# Power_supplies.net
KiCad netlist of a schematic drawn in Altium Designer
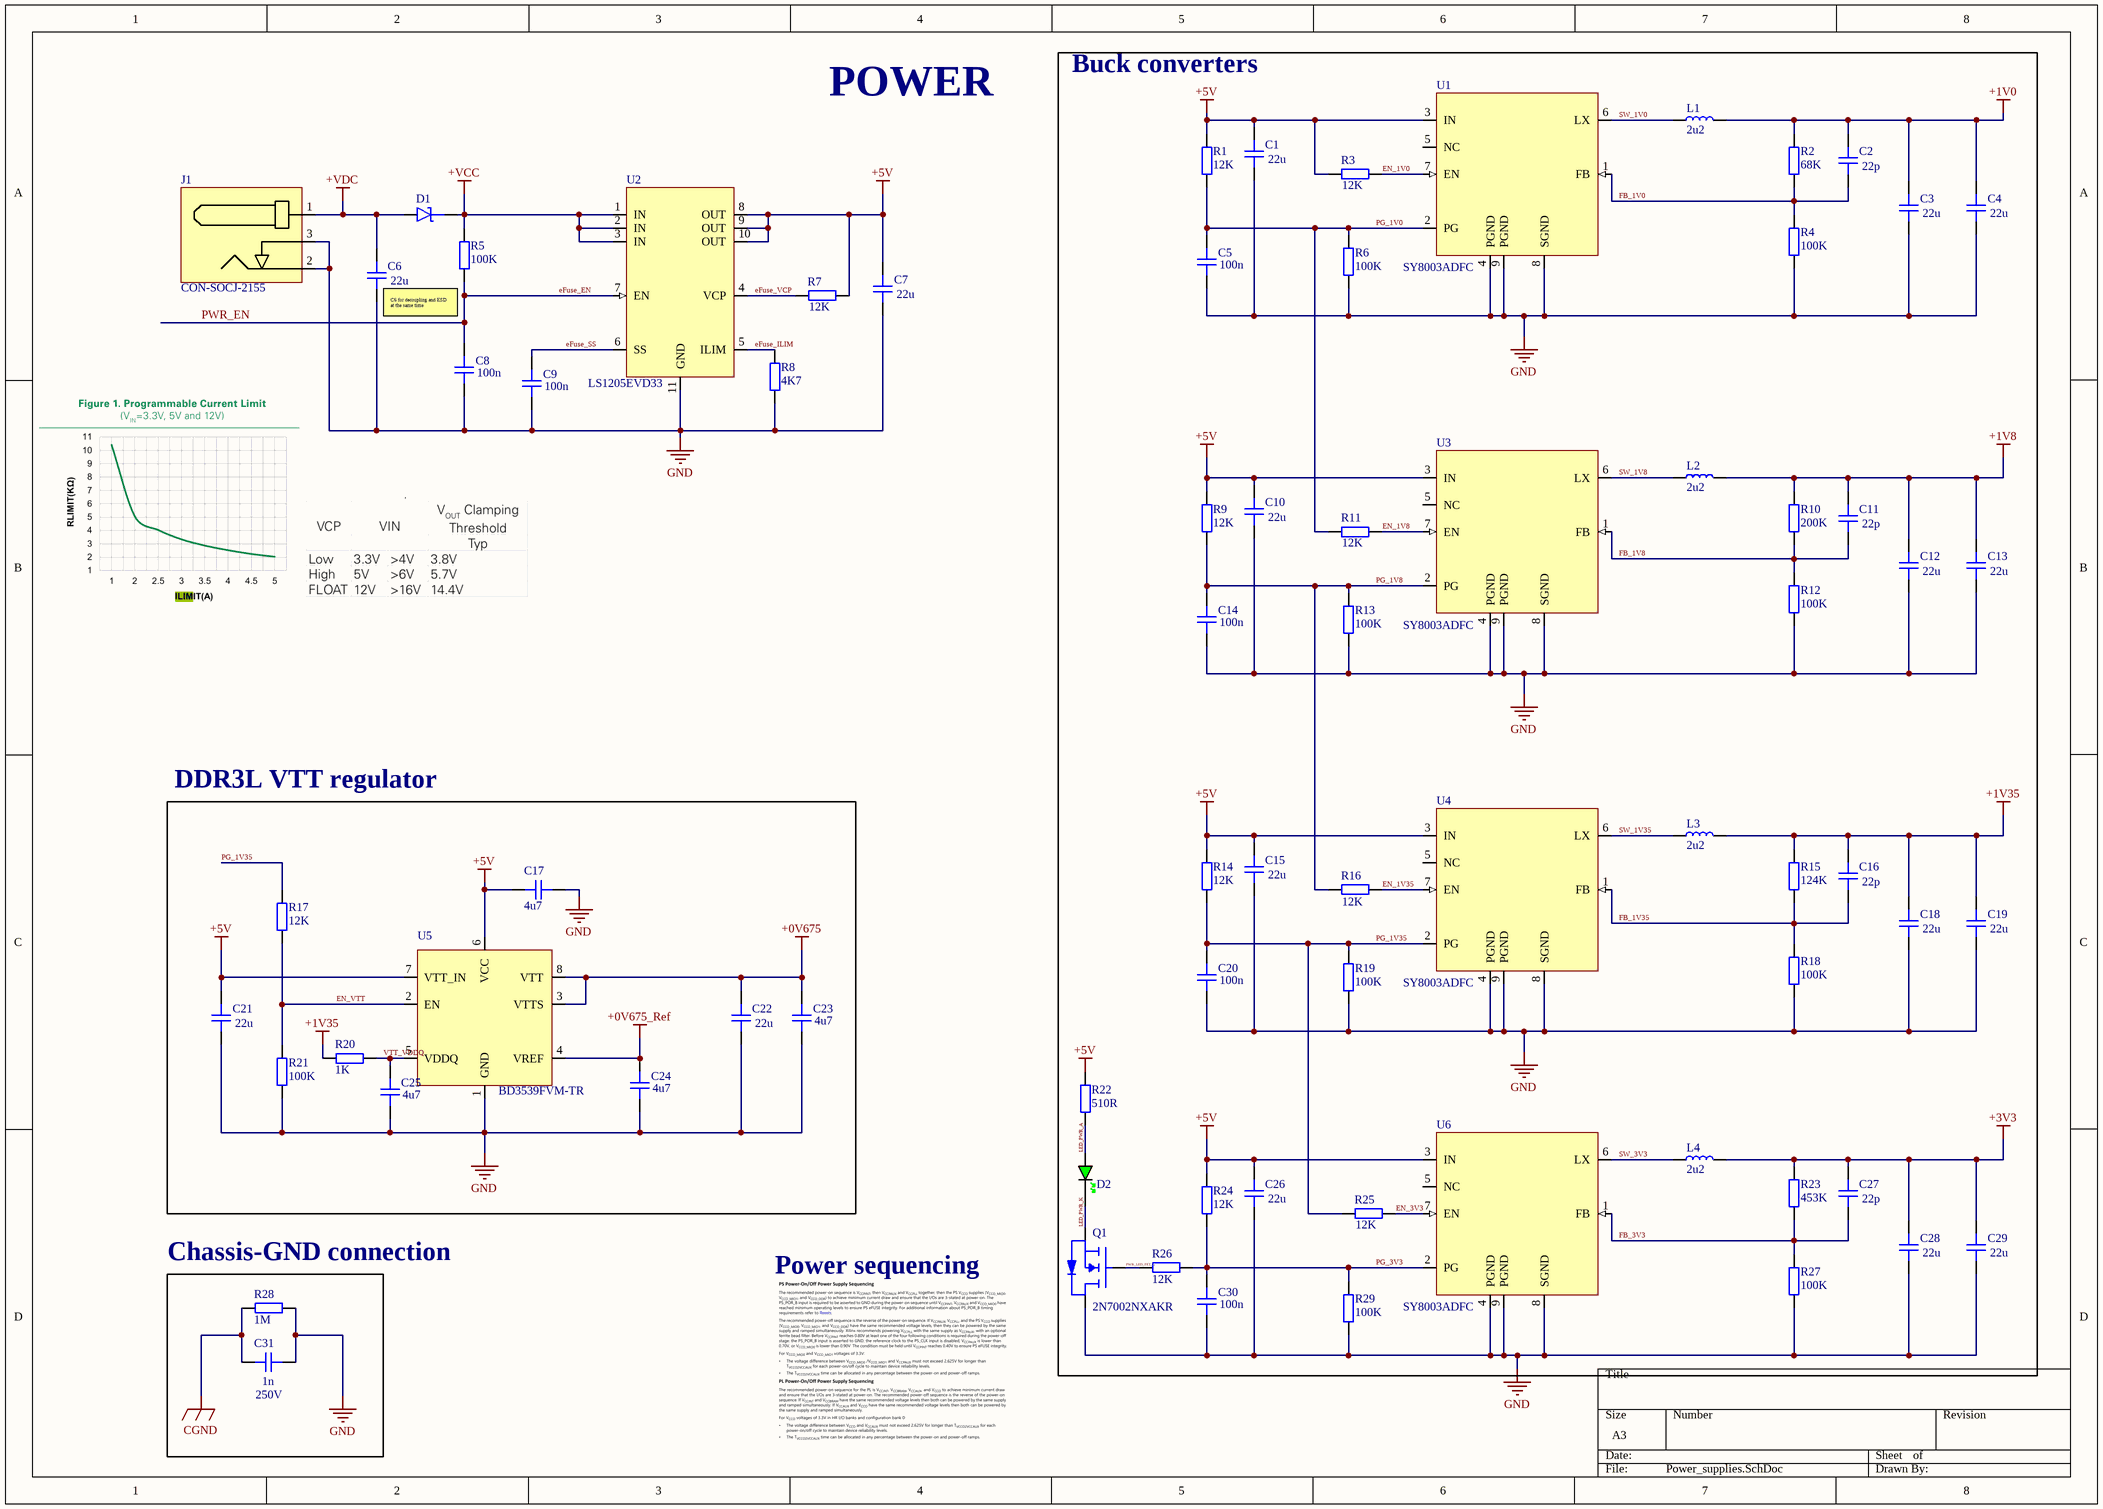
[diagram p0: Power_supplies.SchDoc]

(export (version "E")
  (design (tool "Eeschema 10.0.6"))
  (components
    (comp (ref "C1")
      (value "22u")
      (footprint "CAP_1210")
      (description "Capacitor SMD 1210")
      (fields (field (name "Comment") "C1210"))
      (libsource (lib "Schematic-Lib-PhilsLab") (part "CAP_1210"))
    )
    (comp (ref "C2")
      (value "22p")
      (footprint "CAP_0402")
      (description "Capacitor SMD 0402")
      (fields (field (name "Comment") "C0402"))
      (libsource (lib "Schematic-Lib-PhilsLab") (part "CAP_0402"))
    )
    (comp (ref "C3")
      (value "22u")
      (footprint "CAP_1210")
      (description "Capacitor SMD 1210")
      (fields (field (name "Comment") "C1210"))
      (libsource (lib "Schematic-Lib-PhilsLab") (part "CAP_1210"))
    )
    (comp (ref "C4")
      (value "22u")
      (footprint "CAP_1210")
      (description "Capacitor SMD 1210")
      (fields (field (name "Comment") "C1210"))
      (libsource (lib "Schematic-Lib-PhilsLab") (part "CAP_1210"))
    )
    (comp (ref "C5")
      (value "100n")
      (footprint "CAP_0402")
      (description "Capacitor SMD 0402")
      (fields (field (name "Comment") "C0402"))
      (libsource (lib "Schematic-Lib-PhilsLab") (part "CAP_0402"))
    )
    (comp (ref "C6")
      (value "22u")
      (footprint "CAP_1210")
      (description "Capacitor SMD 1210")
      (fields (field (name "Comment") "C1210"))
      (libsource (lib "Schematic-Lib-PhilsLab") (part "CAP_1210"))
    )
    (comp (ref "C7")
      (value "22u")
      (footprint "CAP_1210")
      (description "Capacitor SMD 1210")
      (fields (field (name "Comment") "C1210"))
      (libsource (lib "Schematic-Lib-PhilsLab") (part "CAP_1210"))
    )
    (comp (ref "C8")
      (value "100n")
      (footprint "CAP_0402")
      (description "Capacitor SMD 0402")
      (fields (field (name "Comment") "C0402"))
      (libsource (lib "Schematic-Lib-PhilsLab") (part "CAP_0402"))
    )
    (comp (ref "C9")
      (value "100n")
      (footprint "CAP_0402")
      (description "Capacitor SMD 0402")
      (fields (field (name "Comment") "C0402"))
      (libsource (lib "Schematic-Lib-PhilsLab") (part "CAP_0402"))
    )
    (comp (ref "C10")
      (value "22u")
      (footprint "CAP_1210")
      (description "Capacitor SMD 1210")
      (fields (field (name "Comment") "C1210"))
      (libsource (lib "Schematic-Lib-PhilsLab") (part "CAP_1210"))
    )
    (comp (ref "C11")
      (value "22p")
      (footprint "CAP_0402")
      (description "Capacitor SMD 0402")
      (fields (field (name "Comment") "C0402"))
      (libsource (lib "Schematic-Lib-PhilsLab") (part "CAP_0402"))
    )
    (comp (ref "C12")
      (value "22u")
      (footprint "CAP_1210")
      (description "Capacitor SMD 1210")
      (fields (field (name "Comment") "C1210"))
      (libsource (lib "Schematic-Lib-PhilsLab") (part "CAP_1210"))
    )
    (comp (ref "C13")
      (value "22u")
      (footprint "CAP_1210")
      (description "Capacitor SMD 1210")
      (fields (field (name "Comment") "C1210"))
      (libsource (lib "Schematic-Lib-PhilsLab") (part "CAP_1210"))
    )
    (comp (ref "C14")
      (value "100n")
      (footprint "CAP_0402")
      (description "Capacitor SMD 0402")
      (fields (field (name "Comment") "C0402"))
      (libsource (lib "Schematic-Lib-PhilsLab") (part "CAP_0402"))
    )
    (comp (ref "C15")
      (value "22u")
      (footprint "CAP_1210")
      (description "Capacitor SMD 1210")
      (fields (field (name "Comment") "C1210"))
      (libsource (lib "Schematic-Lib-PhilsLab") (part "CAP_1210"))
    )
    (comp (ref "C16")
      (value "22p")
      (footprint "CAP_0402")
      (description "Capacitor SMD 0402")
      (fields (field (name "Comment") "C0402"))
      (libsource (lib "Schematic-Lib-PhilsLab") (part "CAP_0402"))
    )
    (comp (ref "C17")
      (value "4u7")
      (footprint "CAP_0402")
      (description "Capacitor SMD 0402")
      (fields (field (name "Comment") "C0402"))
      (libsource (lib "Schematic-Lib-PhilsLab") (part "CAP_0402"))
    )
    (comp (ref "C18")
      (value "22u")
      (footprint "CAP_1210")
      (description "Capacitor SMD 1210")
      (fields (field (name "Comment") "C1210"))
      (libsource (lib "Schematic-Lib-PhilsLab") (part "CAP_1210"))
    )
    (comp (ref "C19")
      (value "22u")
      (footprint "CAP_1210")
      (description "Capacitor SMD 1210")
      (fields (field (name "Comment") "C1210"))
      (libsource (lib "Schematic-Lib-PhilsLab") (part "CAP_1210"))
    )
    (comp (ref "C20")
      (value "100n")
      (footprint "CAP_0402")
      (description "Capacitor SMD 0402")
      (fields (field (name "Comment") "C0402"))
      (libsource (lib "Schematic-Lib-PhilsLab") (part "CAP_0402"))
    )
    (comp (ref "C21")
      (value "22u")
      (footprint "CAP_1210")
      (description "Capacitor SMD 1210")
      (fields (field (name "Comment") "C1210"))
      (libsource (lib "Schematic-Lib-PhilsLab") (part "CAP_1210"))
    )
    (comp (ref "C22")
      (value "22u")
      (footprint "CAP_1210")
      (description "Capacitor SMD 1210")
      (fields (field (name "Comment") "C1210"))
      (libsource (lib "Schematic-Lib-PhilsLab") (part "CAP_1210"))
    )
    (comp (ref "C23")
      (value "4u7")
      (footprint "CAP_0402")
      (description "Capacitor SMD 0402")
      (fields (field (name "Comment") "C0402"))
      (libsource (lib "Schematic-Lib-PhilsLab") (part "CAP_0402"))
    )
    (comp (ref "C24")
      (value "4u7")
      (footprint "CAP_0402")
      (description "Capacitor SMD 0402")
      (fields (field (name "Comment") "C0402"))
      (libsource (lib "Schematic-Lib-PhilsLab") (part "CAP_0402"))
    )
    (comp (ref "C25")
      (value "4u7")
      (footprint "CAP_0402")
      (description "Capacitor SMD 0402")
      (fields (field (name "Comment") "C0402"))
      (libsource (lib "Schematic-Lib-PhilsLab") (part "CAP_0402"))
    )
    (comp (ref "C26")
      (value "22u")
      (footprint "CAP_1210")
      (description "Capacitor SMD 1210")
      (fields (field (name "Comment") "C1210"))
      (libsource (lib "Schematic-Lib-PhilsLab") (part "CAP_1210"))
    )
    (comp (ref "C27")
      (value "22p")
      (footprint "CAP_0402")
      (description "Capacitor SMD 0402")
      (fields (field (name "Comment") "C0402"))
      (libsource (lib "Schematic-Lib-PhilsLab") (part "CAP_0402"))
    )
    (comp (ref "C28")
      (value "22u")
      (footprint "CAP_1210")
      (description "Capacitor SMD 1210")
      (fields (field (name "Comment") "C1210"))
      (libsource (lib "Schematic-Lib-PhilsLab") (part "CAP_1210"))
    )
    (comp (ref "C29")
      (value "22u")
      (footprint "CAP_1210")
      (description "Capacitor SMD 1210")
      (fields (field (name "Comment") "C1210"))
      (libsource (lib "Schematic-Lib-PhilsLab") (part "CAP_1210"))
    )
    (comp (ref "C30")
      (value "100n")
      (footprint "CAP_0402")
      (description "Capacitor SMD 0402")
      (fields (field (name "Comment") "C0402"))
      (libsource (lib "Schematic-Lib-PhilsLab") (part "CAP_0402"))
    )
    (comp (ref "C31")
      (value "1n")
      (footprint "CAP_1206")
      (description "Capacitor SMD 1206")
      (fields (field (name "VOLTAGE") "250V") (field (name "Comment") "C1206"))
      (libsource (lib "Schematic-Lib-PhilsLab") (part "CAP_1206"))
    )
    (comp (ref "D1")
      (value "D_SCHOTTKY_SOD_323")
      (footprint "SOD-323")
      (description "Diode Schottky SMD SOD-323")
      (libsource (lib "Schematic-Lib-PhilsLab") (part "D_SCHOTTKY_SOD_323"))
    )
    (comp (ref "D2")
      (value "GREEN")
      (footprint "LED_0402_GREEN")
      (description "LED 0402 GREEN SMD")
      (libsource (lib "Schematic-Lib-PhilsLab") (part "LED_0402_GREEN"))
    )
    (comp (ref "J1")
      (value "CON-SOCJ-2155")
      (footprint "CON-SOCJ-2155")
      (description "DC Barrell Jack 2.1mm 30V 2.5A THT")
      (fields (field (name "MANUFACTURER") "Gravitech"))
      (libsource (lib "Schematic-Lib-PhilsLab") (part "CON-SOCJ-2155"))
    )
    (comp (ref "L1")
      (value "2u2")
      (footprint "SRP0415")
      (description "Inductor SMD 2.2uH Bourns SRP0415-2R2K")
      (fields (field (name "MANUFACTURER") "Bourns") (field (name "MANUFACTURER PART NUMBER") "SRP0415-2R2K"))
      (libsource (lib "Schematic-Lib-PhilsLab") (part "SRP0415-2R2K"))
    )
    (comp (ref "L2")
      (value "2u2")
      (footprint "SRP0415")
      (description "Inductor SMD 2.2uH Bourns SRP0415-2R2K")
      (fields (field (name "MANUFACTURER") "Bourns") (field (name "MANUFACTURER PART NUMBER") "SRP0415-2R2K"))
      (libsource (lib "Schematic-Lib-PhilsLab") (part "SRP0415-2R2K"))
    )
    (comp (ref "L3")
      (value "2u2")
      (footprint "SRP0415")
      (description "Inductor SMD 2.2uH Bourns SRP0415-2R2K")
      (fields (field (name "MANUFACTURER") "Bourns") (field (name "MANUFACTURER PART NUMBER") "SRP0415-2R2K"))
      (libsource (lib "Schematic-Lib-PhilsLab") (part "SRP0415-2R2K"))
    )
    (comp (ref "L4")
      (value "2u2")
      (footprint "SRP0415")
      (description "Inductor SMD 2.2uH Bourns SRP0415-2R2K")
      (fields (field (name "MANUFACTURER") "Bourns") (field (name "MANUFACTURER PART NUMBER") "SRP0415-2R2K"))
      (libsource (lib "Schematic-Lib-PhilsLab") (part "SRP0415-2R2K"))
    )
    (comp (ref "Q1")
      (value "2N7002NXAKR")
      (footprint "SSM3J338R,LF-SOT23-F")
      (description "MOSFET N-Channel Vds=60V Id=300mA with ESD Protection")
      (fields (field (name "MANUFACTURER") "Nexperia"))
      (libsource (lib "Schematic-Lib-PhilsLab") (part "2N7002NXAKR"))
    )
    (comp (ref "R1")
      (value "12K")
      (footprint "RES_0402")
      (description "Resistor SMD 0402")
      (fields (field (name "Comment") "R0402"))
      (libsource (lib "Schematic-Lib-PhilsLab") (part "RES_0402"))
    )
    (comp (ref "R2")
      (value "68K")
      (footprint "RES_0402")
      (description "Resistor SMD 0402")
      (fields (field (name "Comment") "R0402"))
      (libsource (lib "Schematic-Lib-PhilsLab") (part "RES_0402"))
    )
    (comp (ref "R3")
      (value "12K")
      (footprint "RES_0402")
      (description "Resistor SMD 0402")
      (fields (field (name "Comment") "R0402"))
      (libsource (lib "Schematic-Lib-PhilsLab") (part "RES_0402"))
    )
    (comp (ref "R4")
      (value "100K")
      (footprint "RES_0402")
      (description "Resistor SMD 0402")
      (fields (field (name "Comment") "R0402"))
      (libsource (lib "Schematic-Lib-PhilsLab") (part "RES_0402"))
    )
    (comp (ref "R5")
      (value "100K")
      (footprint "RES_0402")
      (description "Resistor SMD 0402")
      (fields (field (name "Comment") "R0402"))
      (libsource (lib "Schematic-Lib-PhilsLab") (part "RES_0402"))
    )
    (comp (ref "R6")
      (value "100K")
      (footprint "RES_0402")
      (description "Resistor SMD 0402")
      (fields (field (name "Comment") "R0402"))
      (libsource (lib "Schematic-Lib-PhilsLab") (part "RES_0402"))
    )
    (comp (ref "R7")
      (value "12K")
      (footprint "RES_0402")
      (description "Resistor SMD 0402")
      (fields (field (name "Comment") "R0402"))
      (libsource (lib "Schematic-Lib-PhilsLab") (part "RES_0402"))
    )
    (comp (ref "R8")
      (value "4K7")
      (footprint "RES_0402")
      (description "Resistor SMD 0402")
      (fields (field (name "Comment") "R0402"))
      (libsource (lib "Schematic-Lib-PhilsLab") (part "RES_0402"))
    )
    (comp (ref "R9")
      (value "12K")
      (footprint "RES_0402")
      (description "Resistor SMD 0402")
      (fields (field (name "Comment") "R0402"))
      (libsource (lib "Schematic-Lib-PhilsLab") (part "RES_0402"))
    )
    (comp (ref "R10")
      (value "200K")
      (footprint "RES_0402")
      (description "Resistor SMD 0402")
      (fields (field (name "Comment") "R0402"))
      (libsource (lib "Schematic-Lib-PhilsLab") (part "RES_0402"))
    )
    (comp (ref "R11")
      (value "12K")
      (footprint "RES_0402")
      (description "Resistor SMD 0402")
      (fields (field (name "Comment") "R0402"))
      (libsource (lib "Schematic-Lib-PhilsLab") (part "RES_0402"))
    )
    (comp (ref "R12")
      (value "100K")
      (footprint "RES_0402")
      (description "Resistor SMD 0402")
      (fields (field (name "Comment") "R0402"))
      (libsource (lib "Schematic-Lib-PhilsLab") (part "RES_0402"))
    )
    (comp (ref "R13")
      (value "100K")
      (footprint "RES_0402")
      (description "Resistor SMD 0402")
      (fields (field (name "Comment") "R0402"))
      (libsource (lib "Schematic-Lib-PhilsLab") (part "RES_0402"))
    )
    (comp (ref "R14")
      (value "12K")
      (footprint "RES_0402")
      (description "Resistor SMD 0402")
      (fields (field (name "Comment") "R0402"))
      (libsource (lib "Schematic-Lib-PhilsLab") (part "RES_0402"))
    )
    (comp (ref "R15")
      (value "124K")
      (footprint "RES_0402")
      (description "Resistor SMD 0402")
      (fields (field (name "Comment") "R0402"))
      (libsource (lib "Schematic-Lib-PhilsLab") (part "RES_0402"))
    )
    (comp (ref "R16")
      (value "12K")
      (footprint "RES_0402")
      (description "Resistor SMD 0402")
      (fields (field (name "Comment") "R0402"))
      (libsource (lib "Schematic-Lib-PhilsLab") (part "RES_0402"))
    )
    (comp (ref "R17")
      (value "12K")
      (footprint "RES_0402")
      (description "Resistor SMD 0402")
      (fields (field (name "Comment") "R0402"))
      (libsource (lib "Schematic-Lib-PhilsLab") (part "RES_0402"))
    )
    (comp (ref "R18")
      (value "100K")
      (footprint "RES_0402")
      (description "Resistor SMD 0402")
      (fields (field (name "Comment") "R0402"))
      (libsource (lib "Schematic-Lib-PhilsLab") (part "RES_0402"))
    )
    (comp (ref "R19")
      (value "100K")
      (footprint "RES_0402")
      (description "Resistor SMD 0402")
      (fields (field (name "Comment") "R0402"))
      (libsource (lib "Schematic-Lib-PhilsLab") (part "RES_0402"))
    )
    (comp (ref "R20")
      (value "1K")
      (footprint "RES_0402")
      (description "Resistor SMD 0402")
      (fields (field (name "Comment") "R0402"))
      (libsource (lib "Schematic-Lib-PhilsLab") (part "RES_0402"))
    )
    (comp (ref "R21")
      (value "100K")
      (footprint "RES_0402")
      (description "Resistor SMD 0402")
      (fields (field (name "Comment") "R0402"))
      (libsource (lib "Schematic-Lib-PhilsLab") (part "RES_0402"))
    )
    (comp (ref "R22")
      (value "510R")
      (footprint "RES_0402")
      (description "Resistor SMD 0402")
      (fields (field (name "Comment") "R0402"))
      (libsource (lib "Schematic-Lib-PhilsLab") (part "RES_0402"))
    )
    (comp (ref "R23")
      (value "453K")
      (footprint "RES_0402")
      (description "Resistor SMD 0402")
      (fields (field (name "Comment") "R0402"))
      (libsource (lib "Schematic-Lib-PhilsLab") (part "RES_0402"))
    )
    (comp (ref "R24")
      (value "12K")
      (footprint "RES_0402")
      (description "Resistor SMD 0402")
      (fields (field (name "Comment") "R0402"))
      (libsource (lib "Schematic-Lib-PhilsLab") (part "RES_0402"))
    )
    (comp (ref "R25")
      (value "12K")
      (footprint "RES_0402")
      (description "Resistor SMD 0402")
      (fields (field (name "Comment") "R0402"))
      (libsource (lib "Schematic-Lib-PhilsLab") (part "RES_0402"))
    )
    (comp (ref "R26")
      (value "12K")
      (footprint "RES_0402")
      (description "Resistor SMD 0402")
      (fields (field (name "Comment") "R0402"))
      (libsource (lib "Schematic-Lib-PhilsLab") (part "RES_0402"))
    )
    (comp (ref "R27")
      (value "100K")
      (footprint "RES_0402")
      (description "Resistor SMD 0402")
      (fields (field (name "Comment") "R0402"))
      (libsource (lib "Schematic-Lib-PhilsLab") (part "RES_0402"))
    )
    (comp (ref "R28")
      (value "1M")
      (footprint "RES_1206")
      (description "Resistor SMD 1206")
      (libsource (lib "Schematic-Lib-PhilsLab") (part "RES_1206"))
    )
    (comp (ref "R29")
      (value "100K")
      (footprint "RES_0402")
      (description "Resistor SMD 0402")
      (fields (field (name "Comment") "R0402"))
      (libsource (lib "Schematic-Lib-PhilsLab") (part "RES_0402"))
    )
    (comp (ref "U1")
      (value "SY8003ADFC")
      (footprint "DFN2x2-8")
      (description "High Efficiency 5.5V, 3A Continuous, 1MHz Synchronous Step Down Regulator")
      (fields
        (field (name "MANUFACTURER") "Silergy")
        (field (name "MANUFACTURER PART NUMBER") "High Efficiency 5.5V, 3A continuous, 1MHz")
      )
      (libsource (lib "Schematic-Lib-PhilsLab") (part "SY8003ADFC"))
    )
    (comp (ref "U2")
      (value "LS1205EVD33")
      (footprint "DFN3x3_10L")
      (description "18V, 5A eFuse with Programmable Current Limit and Output Voltage Clamp")
      (fields (field (name "MANUFACTURER") "Littelfuse"))
      (libsource (lib "Schematic-Lib-PhilsLab") (part "LS1205EVD33"))
    )
    (comp (ref "U3")
      (value "SY8003ADFC")
      (footprint "DFN2x2-8")
      (description "High Efficiency 5.5V, 3A Continuous, 1MHz Synchronous Step Down Regulator")
      (fields
        (field (name "MANUFACTURER") "Silergy")
        (field (name "MANUFACTURER PART NUMBER") "High Efficiency 5.5V, 3A continuous, 1MHz")
      )
      (libsource (lib "Schematic-Lib-PhilsLab") (part "SY8003ADFC"))
    )
    (comp (ref "U4")
      (value "SY8003ADFC")
      (footprint "DFN2x2-8")
      (description "High Efficiency 5.5V, 3A Continuous, 1MHz Synchronous Step Down Regulator")
      (fields
        (field (name "MANUFACTURER") "Silergy")
        (field (name "MANUFACTURER PART NUMBER") "High Efficiency 5.5V, 3A continuous, 1MHz")
      )
      (libsource (lib "Schematic-Lib-PhilsLab") (part "SY8003ADFC"))
    )
    (comp (ref "U5")
      (value "BD3539FVM-TR")
      (footprint "MSOP8")
      (description "1.0V to 5.5V, 1A 1Ch Termination Regulator for DDR-SDRAMs")
      (fields (field (name "MANUFACTURER") "ROHM Semiconductor"))
      (libsource (lib "Schematic-Lib-PhilsLab") (part "BD3539FVM-TR"))
    )
    (comp (ref "U6")
      (value "SY8003ADFC")
      (footprint "DFN2x2-8")
      (description "High Efficiency 5.5V, 3A Continuous, 1MHz Synchronous Step Down Regulator")
      (fields
        (field (name "MANUFACTURER") "Silergy")
        (field (name "MANUFACTURER PART NUMBER") "High Efficiency 5.5V, 3A continuous, 1MHz")
      )
      (libsource (lib "Schematic-Lib-PhilsLab") (part "SY8003ADFC"))
    )
  )
  (nets
    (net (code "1") (name "+0V675") (class "Default")
      (node (ref "C22") (pin "2") (pinfunction "2_2") (pintype "passive"))
      (node (ref "C23") (pin "2") (pinfunction "2_2") (pintype "passive"))
      (node (ref "U5") (pin "3") (pinfunction "VTTS_3") (pintype "passive"))
      (node (ref "U5") (pin "8") (pinfunction "VTT_8") (pintype "passive"))
    )
    (net (code "2") (name "+0V675_Ref") (class "Default")
      (node (ref "C24") (pin "2") (pinfunction "2_2") (pintype "passive"))
      (node (ref "U5") (pin "4") (pinfunction "VREF_4") (pintype "passive"))
    )
    (net (code "3") (name "+1V0") (class "Default")
      (node (ref "C2") (pin "2") (pinfunction "2_2") (pintype "passive"))
      (node (ref "C3") (pin "2") (pinfunction "2_2") (pintype "passive"))
      (node (ref "C4") (pin "2") (pinfunction "2_2") (pintype "passive"))
      (node (ref "L1") (pin "2") (pinfunction "2_2") (pintype "passive"))
      (node (ref "R2") (pin "2") (pinfunction "2_2") (pintype "passive"))
    )
    (net (code "4") (name "+1V8") (class "Default")
      (node (ref "C11") (pin "2") (pinfunction "2_2") (pintype "passive"))
      (node (ref "C12") (pin "2") (pinfunction "2_2") (pintype "passive"))
      (node (ref "C13") (pin "2") (pinfunction "2_2") (pintype "passive"))
      (node (ref "L2") (pin "2") (pinfunction "2_2") (pintype "passive"))
      (node (ref "R10") (pin "2") (pinfunction "2_2") (pintype "passive"))
    )
    (net (code "5") (name "+1V35") (class "Default")
      (node (ref "C16") (pin "2") (pinfunction "2_2") (pintype "passive"))
      (node (ref "C18") (pin "2") (pinfunction "2_2") (pintype "passive"))
      (node (ref "C19") (pin "2") (pinfunction "2_2") (pintype "passive"))
      (node (ref "L3") (pin "2") (pinfunction "2_2") (pintype "passive"))
      (node (ref "R15") (pin "2") (pinfunction "2_2") (pintype "passive"))
      (node (ref "R20") (pin "2") (pinfunction "2_2") (pintype "passive"))
    )
    (net (code "6") (name "+3V3") (class "Default")
      (node (ref "C27") (pin "2") (pinfunction "2_2") (pintype "passive"))
      (node (ref "C28") (pin "2") (pinfunction "2_2") (pintype "passive"))
      (node (ref "C29") (pin "2") (pinfunction "2_2") (pintype "passive"))
      (node (ref "L4") (pin "2") (pinfunction "2_2") (pintype "passive"))
      (node (ref "R23") (pin "2") (pinfunction "2_2") (pintype "passive"))
    )
    (net (code "7") (name "+5V") (class "Default")
      (node (ref "C1") (pin "2") (pinfunction "2_2") (pintype "passive"))
      (node (ref "C10") (pin "2") (pinfunction "2_2") (pintype "passive"))
      (node (ref "C15") (pin "2") (pinfunction "2_2") (pintype "passive"))
      (node (ref "C17") (pin "2") (pinfunction "2_2") (pintype "passive"))
      (node (ref "C21") (pin "2") (pinfunction "2_2") (pintype "passive"))
      (node (ref "C26") (pin "2") (pinfunction "2_2") (pintype "passive"))
      (node (ref "C7") (pin "2") (pinfunction "2_2") (pintype "passive"))
      (node (ref "R1") (pin "2") (pinfunction "2_2") (pintype "passive"))
      (node (ref "R14") (pin "2") (pinfunction "2_2") (pintype "passive"))
      (node (ref "R22") (pin "2") (pinfunction "2_2") (pintype "passive"))
      (node (ref "R24") (pin "2") (pinfunction "2_2") (pintype "passive"))
      (node (ref "R3") (pin "1") (pinfunction "1_1") (pintype "passive"))
      (node (ref "R7") (pin "2") (pinfunction "2_2") (pintype "passive"))
      (node (ref "R9") (pin "2") (pinfunction "2_2") (pintype "passive"))
      (node (ref "U1") (pin "3") (pinfunction "IN_3") (pintype "power_in"))
      (node (ref "U2") (pin "10") (pinfunction "OUT_10") (pintype "power_in"))
      (node (ref "U2") (pin "8") (pinfunction "OUT_8") (pintype "power_in"))
      (node (ref "U2") (pin "9") (pinfunction "OUT_9") (pintype "power_in"))
      (node (ref "U3") (pin "3") (pinfunction "IN_3") (pintype "power_in"))
      (node (ref "U4") (pin "3") (pinfunction "IN_3") (pintype "power_in"))
      (node (ref "U5") (pin "6") (pinfunction "VCC_6") (pintype "passive"))
      (node (ref "U5") (pin "7") (pinfunction "VTT_IN_7") (pintype "passive"))
      (node (ref "U6") (pin "3") (pinfunction "IN_3") (pintype "power_in"))
    )
    (net (code "8") (name "+VCC") (class "Default")
      (node (ref "D1") (pin "K") (pinfunction "K_K") (pintype "passive"))
      (node (ref "R5") (pin "2") (pinfunction "2_2") (pintype "passive"))
      (node (ref "U2") (pin "1") (pinfunction "IN_1") (pintype "power_in"))
      (node (ref "U2") (pin "2") (pinfunction "IN_2") (pintype "power_in"))
      (node (ref "U2") (pin "3") (pinfunction "IN_3") (pintype "power_in"))
    )
    (net (code "9") (name "+VDC") (class "Default")
      (node (ref "C6") (pin "2") (pinfunction "2_2") (pintype "passive"))
      (node (ref "D1") (pin "A") (pinfunction "A_A") (pintype "passive"))
      (node (ref "J1") (pin "1") (pinfunction "1_1") (pintype "passive"))
    )
    (net (code "10") (name "/EN_1V0") (class "Default")
      (node (ref "R3") (pin "2") (pinfunction "2_2") (pintype "passive"))
      (node (ref "U1") (pin "7") (pinfunction "EN_7") (pintype "input"))
    )
    (net (code "11") (name "/EN_1V8") (class "Default")
      (node (ref "R11") (pin "2") (pinfunction "2_2") (pintype "passive"))
      (node (ref "U3") (pin "7") (pinfunction "EN_7") (pintype "input"))
    )
    (net (code "12") (name "/EN_1V35") (class "Default")
      (node (ref "R16") (pin "2") (pinfunction "2_2") (pintype "passive"))
      (node (ref "U4") (pin "7") (pinfunction "EN_7") (pintype "input"))
    )
    (net (code "13") (name "/EN_3V3") (class "Default")
      (node (ref "R25") (pin "2") (pinfunction "2_2") (pintype "passive"))
      (node (ref "U6") (pin "7") (pinfunction "EN_7") (pintype "input"))
    )
    (net (code "14") (name "/EN_VTT") (class "Default")
      (node (ref "R17") (pin "1") (pinfunction "1_1") (pintype "passive"))
      (node (ref "R21") (pin "2") (pinfunction "2_2") (pintype "passive"))
      (node (ref "U5") (pin "2") (pinfunction "EN_2") (pintype "passive"))
    )
    (net (code "15") (name "/FB_1V0") (class "Default")
      (node (ref "C2") (pin "1") (pinfunction "1_1") (pintype "passive"))
      (node (ref "R2") (pin "1") (pinfunction "1_1") (pintype "passive"))
      (node (ref "R4") (pin "2") (pinfunction "2_2") (pintype "passive"))
      (node (ref "U1") (pin "1") (pinfunction "FB_1") (pintype "input"))
    )
    (net (code "16") (name "/FB_1V8") (class "Default")
      (node (ref "C11") (pin "1") (pinfunction "1_1") (pintype "passive"))
      (node (ref "R10") (pin "1") (pinfunction "1_1") (pintype "passive"))
      (node (ref "R12") (pin "2") (pinfunction "2_2") (pintype "passive"))
      (node (ref "U3") (pin "1") (pinfunction "FB_1") (pintype "input"))
    )
    (net (code "17") (name "/FB_1V35") (class "Default")
      (node (ref "C16") (pin "1") (pinfunction "1_1") (pintype "passive"))
      (node (ref "R15") (pin "1") (pinfunction "1_1") (pintype "passive"))
      (node (ref "R18") (pin "2") (pinfunction "2_2") (pintype "passive"))
      (node (ref "U4") (pin "1") (pinfunction "FB_1") (pintype "input"))
    )
    (net (code "18") (name "/FB_3V3") (class "Default")
      (node (ref "C27") (pin "1") (pinfunction "1_1") (pintype "passive"))
      (node (ref "R23") (pin "1") (pinfunction "1_1") (pintype "passive"))
      (node (ref "R27") (pin "2") (pinfunction "2_2") (pintype "passive"))
      (node (ref "U6") (pin "1") (pinfunction "FB_1") (pintype "input"))
    )
    (net (code "19") (name "/LED_PWR_A") (class "Default")
      (node (ref "D2") (pin "A") (pinfunction "A_A") (pintype "passive"))
      (node (ref "R22") (pin "1") (pinfunction "1_1") (pintype "passive"))
    )
    (net (code "20") (name "/LED_PWR_K") (class "Default")
      (node (ref "D2") (pin "K") (pinfunction "K_K") (pintype "passive"))
      (node (ref "Q1") (pin "S") (pinfunction "S_S") (pintype "passive"))
    )
    (net (code "21") (name "/PG_1V0") (class "Default")
      (node (ref "C5") (pin "2") (pinfunction "2_2") (pintype "passive"))
      (node (ref "R1") (pin "1") (pinfunction "1_1") (pintype "passive"))
      (node (ref "R11") (pin "1") (pinfunction "1_1") (pintype "passive"))
      (node (ref "R6") (pin "2") (pinfunction "2_2") (pintype "passive"))
      (node (ref "U1") (pin "2") (pinfunction "PG_2") (pintype "open_collector"))
    )
    (net (code "22") (name "/PG_1V8") (class "Default")
      (node (ref "C14") (pin "2") (pinfunction "2_2") (pintype "passive"))
      (node (ref "R13") (pin "2") (pinfunction "2_2") (pintype "passive"))
      (node (ref "R16") (pin "1") (pinfunction "1_1") (pintype "passive"))
      (node (ref "R9") (pin "1") (pinfunction "1_1") (pintype "passive"))
      (node (ref "U3") (pin "2") (pinfunction "PG_2") (pintype "open_collector"))
    )
    (net (code "23") (name "/PG_1V35") (class "Default")
      (node (ref "C20") (pin "2") (pinfunction "2_2") (pintype "passive"))
      (node (ref "R14") (pin "1") (pinfunction "1_1") (pintype "passive"))
      (node (ref "R17") (pin "2") (pinfunction "2_2") (pintype "passive"))
      (node (ref "R19") (pin "2") (pinfunction "2_2") (pintype "passive"))
      (node (ref "R25") (pin "1") (pinfunction "1_1") (pintype "passive"))
      (node (ref "U4") (pin "2") (pinfunction "PG_2") (pintype "open_collector"))
    )
    (net (code "24") (name "/PG_3V3") (class "Default")
      (node (ref "C30") (pin "2") (pinfunction "2_2") (pintype "passive"))
      (node (ref "R24") (pin "1") (pinfunction "1_1") (pintype "passive"))
      (node (ref "R26") (pin "1") (pinfunction "1_1") (pintype "passive"))
      (node (ref "R29") (pin "2") (pinfunction "2_2") (pintype "passive"))
      (node (ref "U6") (pin "2") (pinfunction "PG_2") (pintype "open_collector"))
    )
    (net (code "25") (name "/PWR_EN") (class "Default")
      (node (ref "C8") (pin "2") (pinfunction "2_2") (pintype "passive"))
      (node (ref "R5") (pin "1") (pinfunction "1_1") (pintype "passive"))
      (node (ref "U2") (pin "7") (pinfunction "EN_7") (pintype "input"))
    )
    (net (code "26") (name "/PWR_LED_FET_G") (class "Default")
      (node (ref "Q1") (pin "G") (pinfunction "G_G") (pintype "passive"))
      (node (ref "R26") (pin "2") (pinfunction "2_2") (pintype "passive"))
    )
    (net (code "27") (name "/SW_1V0") (class "Default")
      (node (ref "L1") (pin "1") (pinfunction "1_1") (pintype "passive"))
      (node (ref "U1") (pin "6") (pinfunction "LX_6") (pintype "power_in"))
    )
    (net (code "28") (name "/SW_1V8") (class "Default")
      (node (ref "L2") (pin "1") (pinfunction "1_1") (pintype "passive"))
      (node (ref "U3") (pin "6") (pinfunction "LX_6") (pintype "power_in"))
    )
    (net (code "29") (name "/SW_1V35") (class "Default")
      (node (ref "L3") (pin "1") (pinfunction "1_1") (pintype "passive"))
      (node (ref "U4") (pin "6") (pinfunction "LX_6") (pintype "power_in"))
    )
    (net (code "30") (name "/SW_3V3") (class "Default")
      (node (ref "L4") (pin "1") (pinfunction "1_1") (pintype "passive"))
      (node (ref "U6") (pin "6") (pinfunction "LX_6") (pintype "power_in"))
    )
    (net (code "31") (name "/VTT_VDDQ") (class "Default")
      (node (ref "C25") (pin "2") (pinfunction "2_2") (pintype "passive"))
      (node (ref "R20") (pin "1") (pinfunction "1_1") (pintype "passive"))
      (node (ref "U5") (pin "5") (pinfunction "VDDQ_5") (pintype "passive"))
    )
    (net (code "32") (name "/eFuse_ILIM") (class "Default")
      (node (ref "R8") (pin "2") (pinfunction "2_2") (pintype "passive"))
      (node (ref "U2") (pin "5") (pinfunction "ILIM_5") (pintype "passive"))
    )
    (net (code "33") (name "/eFuse_SS") (class "Default")
      (node (ref "C9") (pin "2") (pinfunction "2_2") (pintype "passive"))
      (node (ref "U2") (pin "6") (pinfunction "SS_6") (pintype "passive"))
    )
    (net (code "34") (name "/eFuse_VCP") (class "Default")
      (node (ref "R7") (pin "1") (pinfunction "1_1") (pintype "passive"))
      (node (ref "U2") (pin "4") (pinfunction "VCP_4") (pintype "passive"))
    )
    (net (code "35") (name "CGND") (class "Default")
      (node (ref "C31") (pin "1") (pinfunction "1_1") (pintype "passive"))
      (node (ref "R28") (pin "1") (pinfunction "1_1") (pintype "passive"))
    )
    (net (code "36") (name "GND") (class "Default")
      (node (ref "C1") (pin "1") (pinfunction "1_1") (pintype "passive"))
      (node (ref "C10") (pin "1") (pinfunction "1_1") (pintype "passive"))
      (node (ref "C12") (pin "1") (pinfunction "1_1") (pintype "passive"))
      (node (ref "C13") (pin "1") (pinfunction "1_1") (pintype "passive"))
      (node (ref "C14") (pin "1") (pinfunction "1_1") (pintype "passive"))
      (node (ref "C15") (pin "1") (pinfunction "1_1") (pintype "passive"))
      (node (ref "C17") (pin "1") (pinfunction "1_1") (pintype "passive"))
      (node (ref "C18") (pin "1") (pinfunction "1_1") (pintype "passive"))
      (node (ref "C19") (pin "1") (pinfunction "1_1") (pintype "passive"))
      (node (ref "C20") (pin "1") (pinfunction "1_1") (pintype "passive"))
      (node (ref "C21") (pin "1") (pinfunction "1_1") (pintype "passive"))
      (node (ref "C22") (pin "1") (pinfunction "1_1") (pintype "passive"))
      (node (ref "C23") (pin "1") (pinfunction "1_1") (pintype "passive"))
      (node (ref "C24") (pin "1") (pinfunction "1_1") (pintype "passive"))
      (node (ref "C25") (pin "1") (pinfunction "1_1") (pintype "passive"))
      (node (ref "C26") (pin "1") (pinfunction "1_1") (pintype "passive"))
      (node (ref "C28") (pin "1") (pinfunction "1_1") (pintype "passive"))
      (node (ref "C29") (pin "1") (pinfunction "1_1") (pintype "passive"))
      (node (ref "C3") (pin "1") (pinfunction "1_1") (pintype "passive"))
      (node (ref "C30") (pin "1") (pinfunction "1_1") (pintype "passive"))
      (node (ref "C31") (pin "2") (pinfunction "2_2") (pintype "passive"))
      (node (ref "C4") (pin "1") (pinfunction "1_1") (pintype "passive"))
      (node (ref "C5") (pin "1") (pinfunction "1_1") (pintype "passive"))
      (node (ref "C6") (pin "1") (pinfunction "1_1") (pintype "passive"))
      (node (ref "C7") (pin "1") (pinfunction "1_1") (pintype "passive"))
      (node (ref "C8") (pin "1") (pinfunction "1_1") (pintype "passive"))
      (node (ref "C9") (pin "1") (pinfunction "1_1") (pintype "passive"))
      (node (ref "J1") (pin "2") (pinfunction "2_2") (pintype "passive"))
      (node (ref "J1") (pin "3") (pinfunction "3_3") (pintype "passive"))
      (node (ref "Q1") (pin "D") (pinfunction "D_D") (pintype "passive"))
      (node (ref "R12") (pin "1") (pinfunction "1_1") (pintype "passive"))
      (node (ref "R13") (pin "1") (pinfunction "1_1") (pintype "passive"))
      (node (ref "R18") (pin "1") (pinfunction "1_1") (pintype "passive"))
      (node (ref "R19") (pin "1") (pinfunction "1_1") (pintype "passive"))
      (node (ref "R21") (pin "1") (pinfunction "1_1") (pintype "passive"))
      (node (ref "R27") (pin "1") (pinfunction "1_1") (pintype "passive"))
      (node (ref "R28") (pin "2") (pinfunction "2_2") (pintype "passive"))
      (node (ref "R29") (pin "1") (pinfunction "1_1") (pintype "passive"))
      (node (ref "R4") (pin "1") (pinfunction "1_1") (pintype "passive"))
      (node (ref "R6") (pin "1") (pinfunction "1_1") (pintype "passive"))
      (node (ref "R8") (pin "1") (pinfunction "1_1") (pintype "passive"))
      (node (ref "U1") (pin "4") (pinfunction "PGND_4") (pintype "power_in"))
      (node (ref "U1") (pin "8") (pinfunction "SGND_8") (pintype "power_in"))
      (node (ref "U1") (pin "9") (pinfunction "PGND_9") (pintype "power_in"))
      (node (ref "U2") (pin "11") (pinfunction "GND_11") (pintype "power_in"))
      (node (ref "U3") (pin "4") (pinfunction "PGND_4") (pintype "power_in"))
      (node (ref "U3") (pin "8") (pinfunction "SGND_8") (pintype "power_in"))
      (node (ref "U3") (pin "9") (pinfunction "PGND_9") (pintype "power_in"))
      (node (ref "U4") (pin "4") (pinfunction "PGND_4") (pintype "power_in"))
      (node (ref "U4") (pin "8") (pinfunction "SGND_8") (pintype "power_in"))
      (node (ref "U4") (pin "9") (pinfunction "PGND_9") (pintype "power_in"))
      (node (ref "U5") (pin "1") (pinfunction "GND_1") (pintype "passive"))
      (node (ref "U6") (pin "4") (pinfunction "PGND_4") (pintype "power_in"))
      (node (ref "U6") (pin "8") (pinfunction "SGND_8") (pintype "power_in"))
      (node (ref "U6") (pin "9") (pinfunction "PGND_9") (pintype "power_in"))
    )
    (net (code "37") (name "unconnected-(U1-NC-Pad5)") (class "Default")
      (node (ref "U1") (pin "5") (pinfunction "NC_5") (pintype "passive"))
    )
    (net (code "38") (name "unconnected-(U3-NC-Pad5)") (class "Default")
      (node (ref "U3") (pin "5") (pinfunction "NC_5") (pintype "passive"))
    )
    (net (code "39") (name "unconnected-(U4-NC-Pad5)") (class "Default")
      (node (ref "U4") (pin "5") (pinfunction "NC_5") (pintype "passive"))
    )
    (net (code "40") (name "unconnected-(U6-NC-Pad5)") (class "Default")
      (node (ref "U6") (pin "5") (pinfunction "NC_5") (pintype "passive"))
    )
  )
)
